# LcsNodes-Main-Controller-Board-A_02_04.net
KiCad netlist of a schematic drawn in EasyEDA
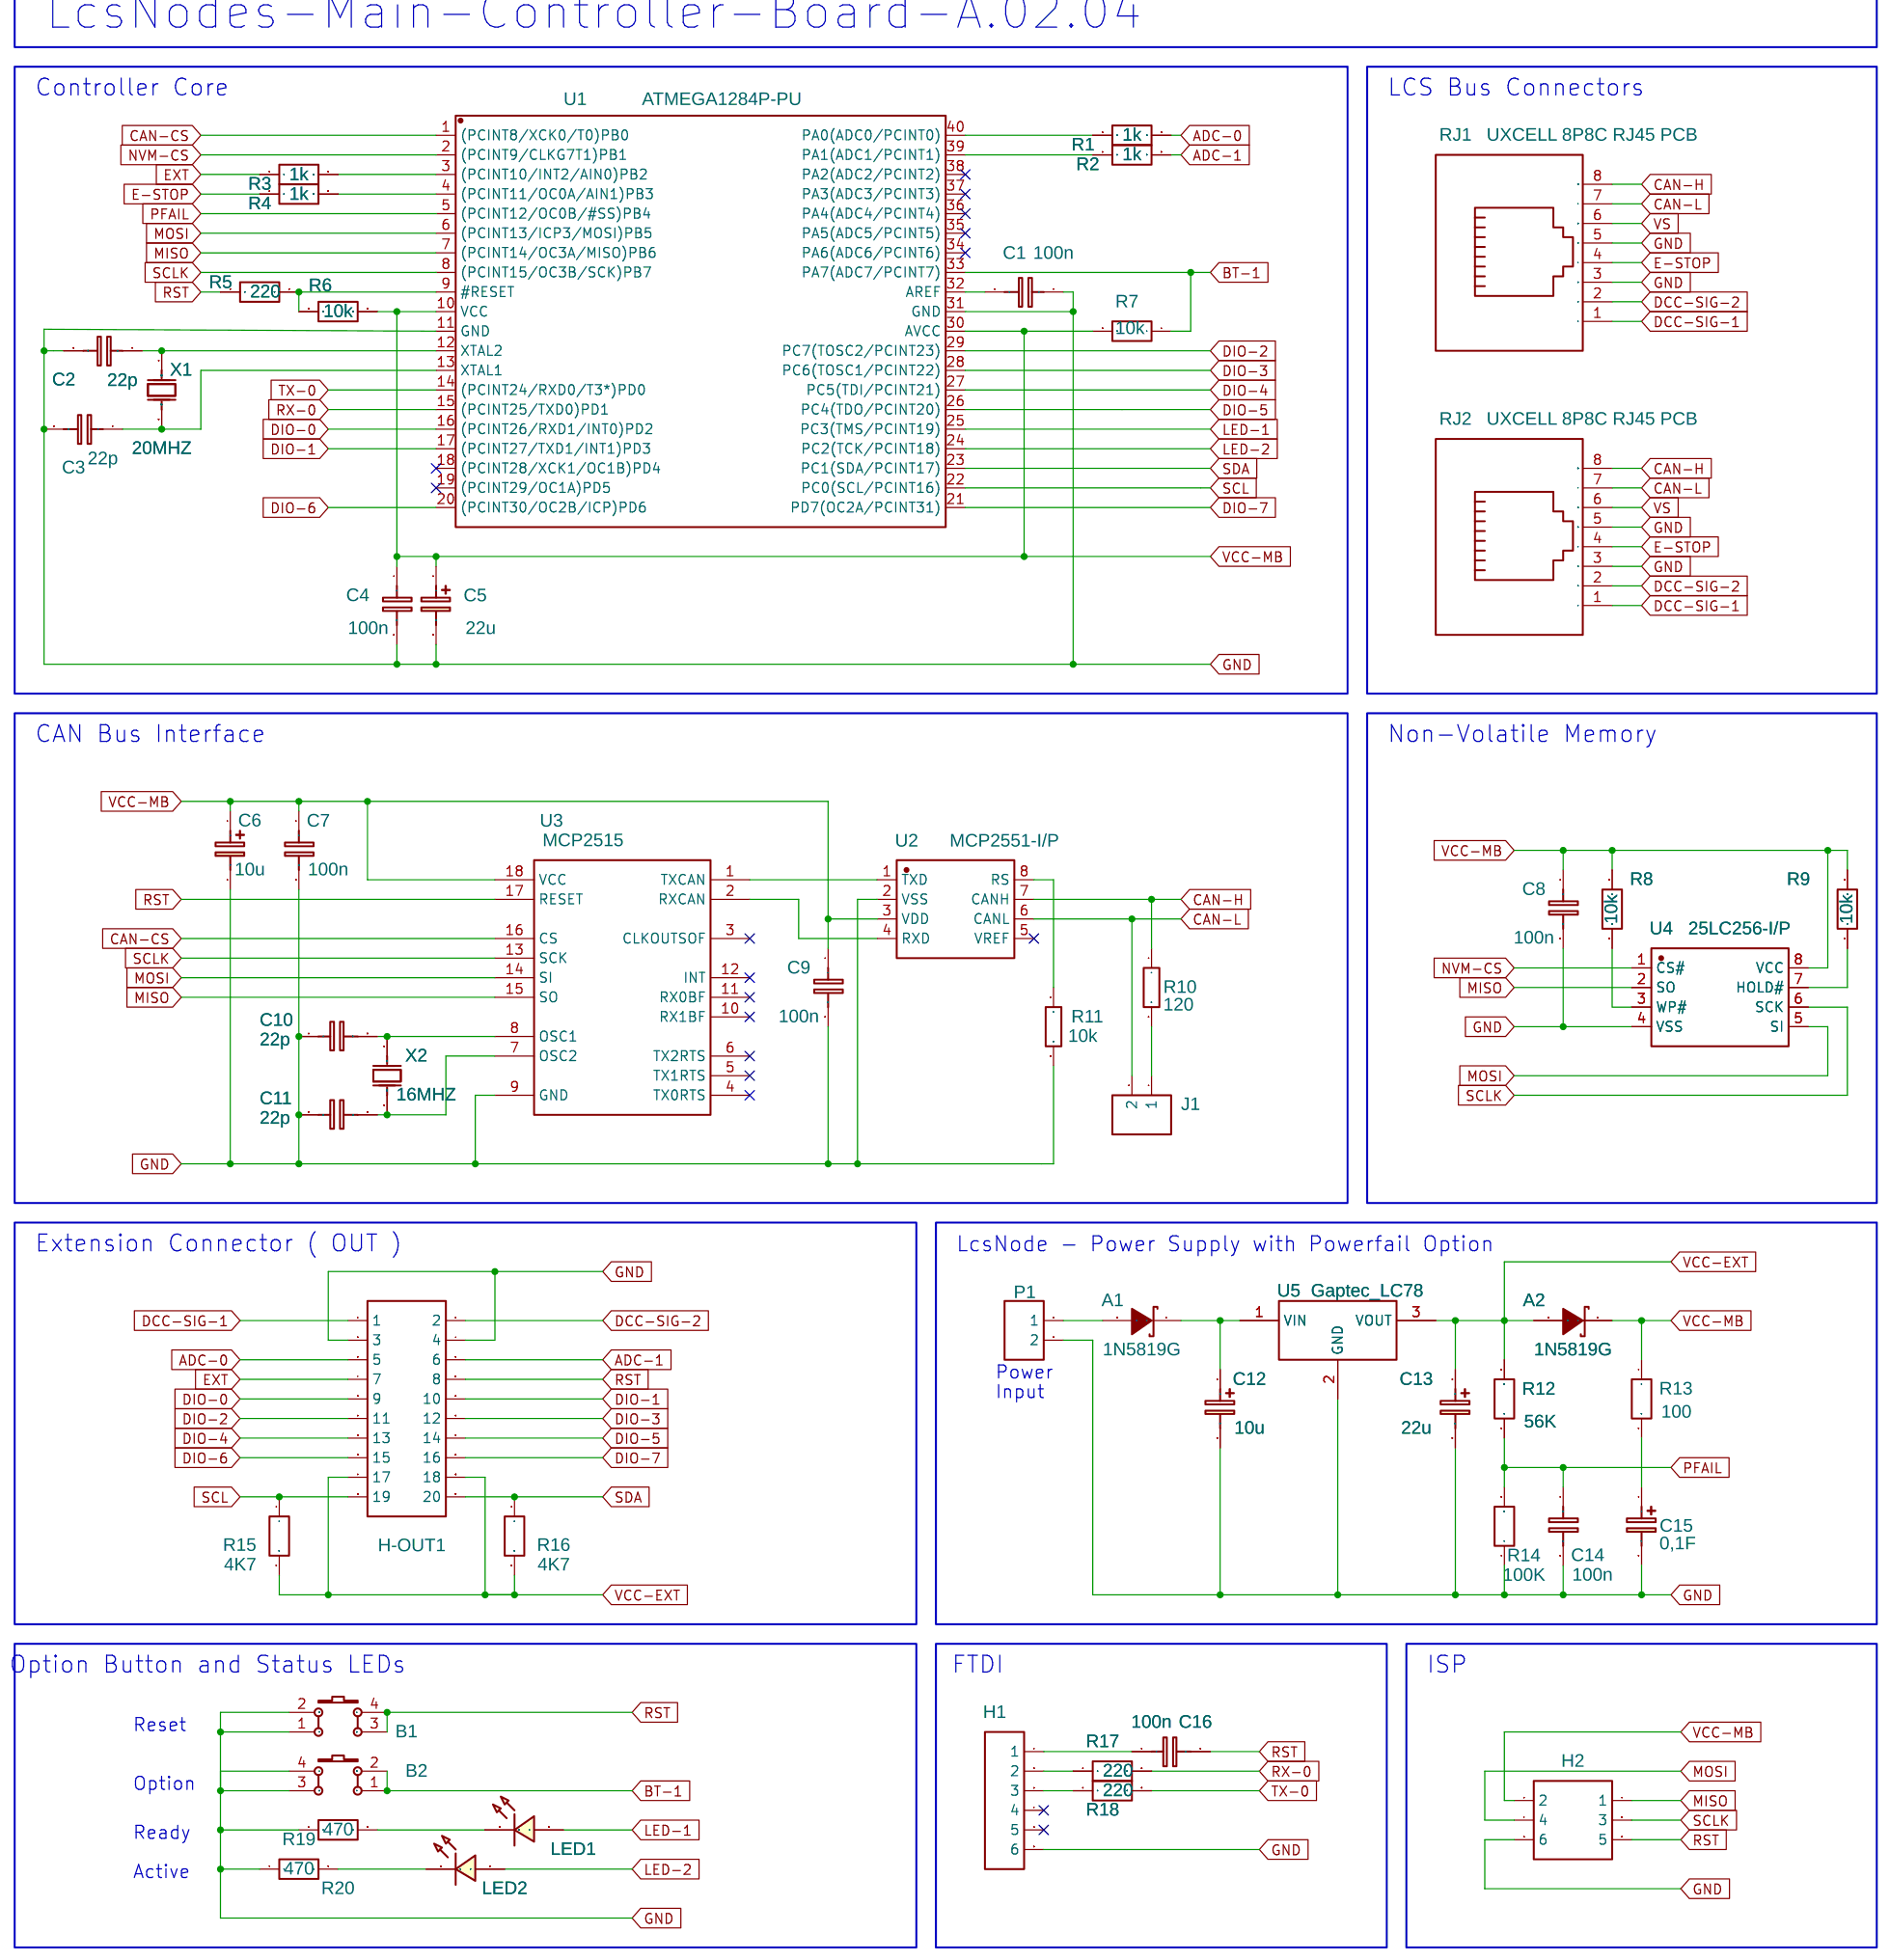
[diagram p0: schematic sheet]

(export (version "E")
  (design (tool "Eeschema 10.0.6"))
  (components
    (comp (ref "A1")
      (value "1N5819G")
      (fields (field (name "BOM_Supplier Part") "1N5819GOS-ND"))
      (libsource (lib "") (part "1N5819G"))
    )
    (comp (ref "A2")
      (value "1N5819G")
      (fields (field (name "BOM_Supplier Part") "1N5819GOS-ND"))
      (libsource (lib "") (part "1N5819G"))
    )
    (comp (ref "B1")
      (value "Reset")
      (fields
        (field (name "BOM_Manufacturer Part") "K2-1102DP-E4SW-04")
        (field (name "BOM_Supplier Part") "C136684")
      )
      (libsource (lib "") (part "K4-6×6_TH_1"))
    )
    (comp (ref "B2")
      (value "Opt")
      (fields
        (field (name "BOM_Manufacturer Part") "K2-1102DP-E4SW-04")
        (field (name "BOM_Supplier Part") "C136684")
      )
      (libsource (lib "") (part "K4-6×6_TH"))
    )
    (comp (ref "C1") (value "100n") (libsource (lib "") (part "C_RAD-0.1_EU")))
    (comp (ref "C2") (value "22p") (libsource (lib "") (part "C_0603_EU_3")))
    (comp (ref "C3") (value "22p") (libsource (lib "") (part "C_0603_EU_3")))
    (comp (ref "C4") (value "100n") (libsource (lib "") (part "C_0603_EU_4")))
    (comp (ref "C5") (value "22u") (libsource (lib "") (part "CE_TH_D4.0×F1.5_EU_2")))
    (comp (ref "C6") (value "10u") (libsource (lib "") (part "CE_TH_D4.0×F1.5_EU")))
    (comp (ref "C7") (value "100n") (libsource (lib "") (part "C_0603_EU_4")))
    (comp (ref "C8") (value "100n") (libsource (lib "") (part "C_0603_EU_2")))
    (comp (ref "C9") (value "100n") (libsource (lib "") (part "C_0603_EU_4")))
    (comp (ref "C10") (value "22p") (libsource (lib "") (part "C_0603_EU_1")))
    (comp (ref "C11") (value "22p") (libsource (lib "") (part "C_0603_EU_1")))
    (comp (ref "C12") (value "10u") (libsource (lib "") (part "CE_TH_D4.0×F1.5_EU_1")))
    (comp (ref "C13") (value "22u") (libsource (lib "") (part "CE_TH_D4.0×F1.5_EU_1")))
    (comp (ref "C14") (value "100n") (libsource (lib "") (part "C_RAD-0.2_EU")))
    (comp (ref "C15") (value "0,1F") (libsource (lib "") (part "C_Tan_SMD_A_EU")))
    (comp (ref "C16") (value "100n") (libsource (lib "") (part "C_0603_EU")))
    (comp (ref "H-OUT1")
      (value "HDR-F-2.54_2x10")
      (fields (field (name "BOM_Supplier Part") "C30867"))
      (libsource (lib "") (part "HDR-F-2.54_2x10"))
    )
    (comp (ref "H1")
      (value "HDR-F-2.54_1x6")
      (fields (field (name "BOM_Supplier Part") "C40877"))
      (libsource (lib "") (part "HDR-F-2.54_1x6"))
    )
    (comp (ref "H2")
      (value "HDR-F-2.54_2x3")
      (fields (field (name "BOM_Supplier Part") "C65114"))
      (libsource (lib "") (part "HDR-F-2.54_2x3"))
    )
    (comp (ref "J1")
      (value "HDR-M-2.54_1x2")
      (fields (field (name "BOM_Supplier Part") "C124375"))
      (libsource (lib "") (part "HDR-M-2.54_1x2"))
    )
    (comp (ref "LED1")
      (value "LED-TH-3mm_R")
      (fields
        (field (name "BOM_Manufacturer Part") "204-10SDRD/S530-A3-L")
        (field (name "BOM_Supplier Part") "C84774")
      )
      (libsource (lib "") (part "LED-TH-3mm_R"))
    )
    (comp (ref "LED2")
      (value "LED-TH-3mm_R")
      (fields
        (field (name "BOM_Manufacturer Part") "204-10SDRD/S530-A3-L")
        (field (name "BOM_Supplier Part") "C84774")
      )
      (libsource (lib "") (part "LED-TH-3mm_R"))
    )
    (comp (ref "P1") (value "CONN-TH_2P-P5.08") (libsource (lib "") (part "CONN-TH_2P-P5.08")))
    (comp (ref "R1") (value "1k") (libsource (lib "") (part "R_AXIAL-0.3_EU")))
    (comp (ref "R2") (value "1k") (libsource (lib "") (part "R_AXIAL-0.3_EU")))
    (comp (ref "R3") (value "1k") (libsource (lib "") (part "R_AXIAL-0.3_EU")))
    (comp (ref "R4") (value "1k") (libsource (lib "") (part "R_AXIAL-0.3_EU")))
    (comp (ref "R5") (value "220") (libsource (lib "") (part "R_AXIAL-0.3_EU")))
    (comp (ref "R6") (value "10k") (libsource (lib "") (part "R_AXIAL-0.3_EU")))
    (comp (ref "R7") (value "10k") (libsource (lib "") (part "R_AXIAL-0.3_EU_2")))
    (comp (ref "R8") (value "10k") (libsource (lib "") (part "R_AXIAL-0.3_EU_1")))
    (comp (ref "R9") (value "10k") (libsource (lib "") (part "R_AXIAL-0.3_EU_3")))
    (comp (ref "R10") (value "120") (libsource (lib "") (part "RESISTOR-AXIAL-0.1")))
    (comp (ref "R11") (value "10k") (libsource (lib "") (part "RESISTOR-AXIAL-0.1")))
    (comp (ref "R12") (value "56K") (libsource (lib "") (part "R_AXIAL-0.3_EU_3")))
    (comp (ref "R13") (value "100") (libsource (lib "") (part "R_AXIAL-0.3_EU_1")))
    (comp (ref "R14") (value "100K") (libsource (lib "") (part "R_AXIAL-0.3_EU_3")))
    (comp (ref "R15") (value "4K7") (libsource (lib "") (part "R_AXIAL-0.3_EU_1")))
    (comp (ref "R16") (value "4K7") (libsource (lib "") (part "R_AXIAL-0.3_EU_1")))
    (comp (ref "R17") (value "220") (libsource (lib "") (part "R_AXIAL-0.3_EU")))
    (comp (ref "R18") (value "220") (libsource (lib "") (part "R_AXIAL-0.3_EU")))
    (comp (ref "R19") (value "470") (libsource (lib "") (part "R_AXIAL-0.3_EU")))
    (comp (ref "R20") (value "470") (libsource (lib "") (part "R_AXIAL-0.3_EU")))
    (comp (ref "RJ1")
      (value "UXCELL 8P8C RJ45 PCB")
      (fields
        (field (name "BOM_Manufacturer Part") "R-RJ45R10P-B000")
        (field (name "BOM_Supplier Part") "C386758")
      )
      (libsource (lib "") (part "UXCELL 8P8C RJ45 PCB"))
    )
    (comp (ref "RJ2")
      (value "UXCELL 8P8C RJ45 PCB")
      (fields
        (field (name "BOM_Manufacturer Part") "R-RJ45R10P-B000")
        (field (name "BOM_Supplier Part") "C386758")
      )
      (libsource (lib "") (part "UXCELL 8P8C RJ45 PCB"))
    )
    (comp (ref "U1")
      (value "ATMEGA1284P-PU")
      (fields (field (name "BOM_Supplier Part") "C116839"))
      (libsource (lib "") (part "ATMEGA1284P-PU"))
    )
    (comp (ref "U2")
      (value "MCP2551-I/P")
      (fields (field (name "BOM_Supplier Part") "C411627"))
      (libsource (lib "") (part "MCP2551-I/P"))
    )
    (comp (ref "U3") (value "MCP2515") (libsource (lib "") (part "MCP2515")))
    (comp (ref "U4")
      (value "25LC256-I/P")
      (fields (field (name "BOM_Supplier Part") "C511271"))
      (libsource (lib "") (part "25LC256-I/P"))
    )
    (comp (ref "U5") (value "Gaptec_LC78") (libsource (lib "") (part "Gaptec_LC78")))
    (comp (ref "X1")
      (value "20MHZ")
      (fields
        (field (name "BOM_Manufacturer Part") "X49SD16MSD2SC")
        (field (name "BOM_Supplier Part") "C16212")
      )
      (libsource (lib "") (part "16MHZ"))
    )
    (comp (ref "X2")
      (value "16MHZ")
      (fields
        (field (name "BOM_Manufacturer Part") "X49SD16MSD2SC")
        (field (name "BOM_Supplier Part") "C16212")
      )
      (libsource (lib "") (part "16MHZ"))
    )
  )
  (nets
    (net (code "1") (name "ADC-0") (class "Default")
      (node (ref "H-OUT1") (pin "5") (pinfunction "5_5") (pintype "input"))
      (node (ref "R1") (pin "2") (pinfunction "2_2") (pintype "unspecified"))
    )
    (net (code "2") (name "ADC-1") (class "Default")
      (node (ref "H-OUT1") (pin "6") (pinfunction "6_6") (pintype "input"))
      (node (ref "R2") (pin "2") (pinfunction "2_2") (pintype "unspecified"))
    )
    (net (code "3") (name "BT-1") (class "Default")
      (node (ref "B2") (pin "1") (pinfunction "1_1") (pintype "unspecified"))
      (node (ref "B2") (pin "2") (pinfunction "2_2") (pintype "unspecified"))
      (node (ref "R7") (pin "1") (pinfunction "1_1") (pintype "unspecified"))
      (node (ref "U1") (pin "33") (pinfunction "PA7(ADC7/PCINT7)_33") (pintype "unspecified"))
    )
    (net (code "4") (name "CAN-CS") (class "Default")
      (node (ref "U1") (pin "1") (pinfunction "(PCINT8/XCK0/T0)PB0_1") (pintype "unspecified"))
      (node (ref "U3") (pin "16") (pinfunction "CS_16") (pintype "unspecified"))
    )
    (net (code "5") (name "CAN-H") (class "Default")
      (node (ref "R10") (pin "1") (pinfunction "1_1") (pintype "input"))
      (node (ref "RJ1") (pin "8") (pinfunction "8_8") (pintype "unspecified"))
      (node (ref "RJ2") (pin "8") (pinfunction "8_8") (pintype "unspecified"))
      (node (ref "U2") (pin "7") (pinfunction "CANH_7") (pintype "unspecified"))
    )
    (net (code "6") (name "CAN-L") (class "Default")
      (node (ref "J1") (pin "2") (pinfunction "2_2") (pintype "unspecified"))
      (node (ref "RJ1") (pin "7") (pinfunction "7_7") (pintype "unspecified"))
      (node (ref "RJ2") (pin "7") (pinfunction "7_7") (pintype "unspecified"))
      (node (ref "U2") (pin "6") (pinfunction "CANL_6") (pintype "unspecified"))
    )
    (net (code "7") (name "DCC-SIG-1") (class "Default")
      (node (ref "H-OUT1") (pin "1") (pinfunction "1_1") (pintype "input"))
      (node (ref "RJ1") (pin "1") (pinfunction "1_1") (pintype "unspecified"))
      (node (ref "RJ2") (pin "1") (pinfunction "1_1") (pintype "unspecified"))
    )
    (net (code "8") (name "DCC-SIG-2") (class "Default")
      (node (ref "H-OUT1") (pin "2") (pinfunction "2_2") (pintype "input"))
      (node (ref "RJ1") (pin "2") (pinfunction "2_2") (pintype "unspecified"))
      (node (ref "RJ2") (pin "2") (pinfunction "2_2") (pintype "unspecified"))
    )
    (net (code "9") (name "DIO-0") (class "Default")
      (node (ref "H-OUT1") (pin "9") (pinfunction "9_9") (pintype "input"))
      (node (ref "U1") (pin "16") (pinfunction "(PCINT26/RXD1/INT0)PD2_16") (pintype "unspecified"))
    )
    (net (code "10") (name "DIO-1") (class "Default")
      (node (ref "H-OUT1") (pin "10") (pinfunction "10_10") (pintype "input"))
      (node (ref "U1") (pin "17") (pinfunction "(PCINT27/TXD1/INT1)PD3_17") (pintype "unspecified"))
    )
    (net (code "11") (name "DIO-2") (class "Default")
      (node (ref "H-OUT1") (pin "11") (pinfunction "11_11") (pintype "input"))
      (node (ref "U1") (pin "29") (pinfunction "PC7(TOSC2/PCINT23)_29") (pintype "unspecified"))
    )
    (net (code "12") (name "DIO-3") (class "Default")
      (node (ref "H-OUT1") (pin "12") (pinfunction "12_12") (pintype "input"))
      (node (ref "U1") (pin "28") (pinfunction "PC6(TOSC1/PCINT22)_28") (pintype "unspecified"))
    )
    (net (code "13") (name "DIO-4") (class "Default")
      (node (ref "H-OUT1") (pin "13") (pinfunction "13_13") (pintype "input"))
      (node (ref "U1") (pin "27") (pinfunction "PC5(TDI/PCINT21)_27") (pintype "unspecified"))
    )
    (net (code "14") (name "DIO-5") (class "Default")
      (node (ref "H-OUT1") (pin "14") (pinfunction "14_14") (pintype "input"))
      (node (ref "U1") (pin "26") (pinfunction "PC4(TDO/PCINT20)_26") (pintype "unspecified"))
    )
    (net (code "15") (name "DIO-6") (class "Default")
      (node (ref "H-OUT1") (pin "15") (pinfunction "15_15") (pintype "input"))
      (node (ref "U1") (pin "20") (pinfunction "(PCINT30/OC2B/ICP)PD6_20") (pintype "unspecified"))
    )
    (net (code "16") (name "DIO-7") (class "Default")
      (node (ref "H-OUT1") (pin "16") (pinfunction "16_16") (pintype "input"))
      (node (ref "U1") (pin "21") (pinfunction "PD7(OC2A/PCINT31)_21") (pintype "unspecified"))
    )
    (net (code "17") (name "E-STOP") (class "Default")
      (node (ref "R4") (pin "1") (pinfunction "1_1") (pintype "unspecified"))
      (node (ref "RJ1") (pin "4") (pinfunction "4_4") (pintype "unspecified"))
      (node (ref "RJ2") (pin "4") (pinfunction "4_4") (pintype "unspecified"))
    )
    (net (code "18") (name "EXT") (class "Default")
      (node (ref "H-OUT1") (pin "7") (pinfunction "7_7") (pintype "input"))
      (node (ref "R3") (pin "1") (pinfunction "1_1") (pintype "unspecified"))
    )
    (net (code "19") (name "GND") (class "Default")
      (node (ref "B1") (pin "1") (pinfunction "1_1") (pintype "unspecified"))
      (node (ref "B1") (pin "2") (pinfunction "2_2") (pintype "unspecified"))
      (node (ref "B2") (pin "3") (pinfunction "3_3") (pintype "unspecified"))
      (node (ref "B2") (pin "4") (pinfunction "4_4") (pintype "unspecified"))
      (node (ref "C1") (pin "1") (pinfunction "1_1") (pintype "unspecified"))
      (node (ref "C10") (pin "1") (pinfunction "1_1") (pintype "unspecified"))
      (node (ref "C11") (pin "1") (pinfunction "1_1") (pintype "unspecified"))
      (node (ref "C12") (pin "2") (pinfunction "2_2") (pintype "unspecified"))
      (node (ref "C13") (pin "2") (pinfunction "2_2") (pintype "unspecified"))
      (node (ref "C14") (pin "2") (pinfunction "2_2") (pintype "unspecified"))
      (node (ref "C15") (pin "2") (pinfunction "2_2") (pintype "unspecified"))
      (node (ref "C2") (pin "2") (pinfunction "2_2") (pintype "unspecified"))
      (node (ref "C3") (pin "2") (pinfunction "2_2") (pintype "unspecified"))
      (node (ref "C4") (pin "2") (pinfunction "2_2") (pintype "unspecified"))
      (node (ref "C5") (pin "2") (pinfunction "2_2") (pintype "unspecified"))
      (node (ref "C6") (pin "2") (pinfunction "2_2") (pintype "unspecified"))
      (node (ref "C7") (pin "2") (pinfunction "2_2") (pintype "unspecified"))
      (node (ref "C8") (pin "2") (pinfunction "2_2") (pintype "unspecified"))
      (node (ref "C9") (pin "2") (pinfunction "2_2") (pintype "unspecified"))
      (node (ref "H-OUT1") (pin "3") (pinfunction "3_3") (pintype "input"))
      (node (ref "H-OUT1") (pin "4") (pinfunction "4_4") (pintype "input"))
      (node (ref "H1") (pin "6") (pinfunction "6_6") (pintype "input"))
      (node (ref "H2") (pin "6") (pinfunction "6_6") (pintype "input"))
      (node (ref "P1") (pin "2") (pinfunction "2_2") (pintype "unspecified"))
      (node (ref "R11") (pin "2") (pinfunction "2_2") (pintype "input"))
      (node (ref "R14") (pin "1") (pinfunction "1_1") (pintype "unspecified"))
      (node (ref "R19") (pin "1") (pinfunction "1_1") (pintype "unspecified"))
      (node (ref "R20") (pin "1") (pinfunction "1_1") (pintype "unspecified"))
      (node (ref "RJ1") (pin "3") (pinfunction "3_3") (pintype "unspecified"))
      (node (ref "RJ1") (pin "5") (pinfunction "5_5") (pintype "unspecified"))
      (node (ref "RJ2") (pin "3") (pinfunction "3_3") (pintype "unspecified"))
      (node (ref "RJ2") (pin "5") (pinfunction "5_5") (pintype "unspecified"))
      (node (ref "U1") (pin "11") (pinfunction "GND_11") (pintype "unspecified"))
      (node (ref "U1") (pin "31") (pinfunction "GND_31") (pintype "unspecified"))
      (node (ref "U2") (pin "2") (pinfunction "VSS_2") (pintype "unspecified"))
      (node (ref "U3") (pin "9") (pinfunction "GND_9") (pintype "passive"))
      (node (ref "U4") (pin "4") (pinfunction "VSS_4") (pintype "unspecified"))
      (node (ref "U5") (pin "2") (pinfunction "GND_2") (pintype "unspecified"))
    )
    (net (code "20") (name "LED-1") (class "Default")
      (node (ref "LED1") (pin "1") (pinfunction "1_1") (pintype "unspecified"))
      (node (ref "U1") (pin "25") (pinfunction "PC3(TMS/PCINT19)_25") (pintype "unspecified"))
    )
    (net (code "21") (name "LED-2") (class "Default")
      (node (ref "LED2") (pin "1") (pinfunction "1_1") (pintype "unspecified"))
      (node (ref "U1") (pin "24") (pinfunction "PC2(TCK/PCINT18)_24") (pintype "unspecified"))
    )
    (net (code "22") (name "MISO") (class "Default")
      (node (ref "H2") (pin "1") (pinfunction "1_1") (pintype "input"))
      (node (ref "U1") (pin "7") (pinfunction "(PCINT14/OC3A/MISO)PB6_7") (pintype "unspecified"))
      (node (ref "U3") (pin "15") (pinfunction "SO_15") (pintype "output"))
      (node (ref "U4") (pin "2") (pinfunction "SO_2") (pintype "unspecified"))
    )
    (net (code "23") (name "MOSI") (class "Default")
      (node (ref "H2") (pin "4") (pinfunction "4_4") (pintype "input"))
      (node (ref "U1") (pin "6") (pinfunction "(PCINT13/ICP3/MOSI)PB5_6") (pintype "unspecified"))
      (node (ref "U3") (pin "14") (pinfunction "SI_14") (pintype "unspecified"))
      (node (ref "U4") (pin "5") (pinfunction "SI_5") (pintype "unspecified"))
    )
    (net (code "24") (name "NVM-CS") (class "Default")
      (node (ref "U1") (pin "2") (pinfunction "(PCINT9/CLKG7T1)PB1_2") (pintype "unspecified"))
      (node (ref "U4") (pin "1") (pinfunction "CS#_1") (pintype "unspecified"))
    )
    (net (code "25") (name "Net-(A1-A)") (class "Default")
      (node (ref "A1") (pin "2") (pinfunction "A_2") (pintype "unspecified"))
      (node (ref "P1") (pin "1") (pinfunction "1_1") (pintype "unspecified"))
    )
    (net (code "26") (name "Net-(A1-K)") (class "Default")
      (node (ref "A1") (pin "1") (pinfunction "K_1") (pintype "unspecified"))
      (node (ref "C12") (pin "1") (pinfunction "1_1") (pintype "unspecified"))
      (node (ref "U5") (pin "1") (pinfunction "VIN_1") (pintype "unspecified"))
    )
    (net (code "27") (name "Net-(C15-Pad1)") (class "Default")
      (node (ref "C15") (pin "1") (pinfunction "1_1") (pintype "unspecified"))
      (node (ref "R13") (pin "2") (pinfunction "2_2") (pintype "unspecified"))
    )
    (net (code "28") (name "Net-(C16-Pad1)") (class "Default")
      (node (ref "C16") (pin "1") (pinfunction "1_1") (pintype "unspecified"))
      (node (ref "H1") (pin "1") (pinfunction "1_1") (pintype "input"))
    )
    (net (code "29") (name "Net-(H1-Pad2)") (class "Default")
      (node (ref "H1") (pin "2") (pinfunction "2_2") (pintype "input"))
      (node (ref "R17") (pin "1") (pinfunction "1_1") (pintype "unspecified"))
    )
    (net (code "30") (name "Net-(H1-Pad3)") (class "Default")
      (node (ref "H1") (pin "3") (pinfunction "3_3") (pintype "input"))
      (node (ref "R18") (pin "1") (pinfunction "1_1") (pintype "unspecified"))
    )
    (net (code "31") (name "Net-(J1-Pad1)") (class "Default")
      (node (ref "J1") (pin "1") (pinfunction "1_1") (pintype "unspecified"))
      (node (ref "R10") (pin "2") (pinfunction "2_2") (pintype "input"))
    )
    (net (code "32") (name "Net-(LED1-Pad2)") (class "Default")
      (node (ref "LED1") (pin "2") (pinfunction "2_2") (pintype "unspecified"))
      (node (ref "R19") (pin "2") (pinfunction "2_2") (pintype "unspecified"))
    )
    (net (code "33") (name "Net-(LED2-Pad2)") (class "Default")
      (node (ref "LED2") (pin "2") (pinfunction "2_2") (pintype "unspecified"))
      (node (ref "R20") (pin "2") (pinfunction "2_2") (pintype "unspecified"))
    )
    (net (code "34") (name "Net-(U1-#RESET)") (class "Default")
      (node (ref "R5") (pin "2") (pinfunction "2_2") (pintype "unspecified"))
      (node (ref "R6") (pin "1") (pinfunction "1_1") (pintype "unspecified"))
      (node (ref "U1") (pin "9") (pinfunction "#RESET_9") (pintype "unspecified"))
    )
    (net (code "35") (name "Net-(U1-(PCINT10{slash}INT2{slash}AIN0)PB2)") (class "Default")
      (node (ref "R3") (pin "2") (pinfunction "2_2") (pintype "unspecified"))
      (node (ref "U1") (pin "3") (pinfunction "(PCINT10/INT2/AIN0)PB2_3") (pintype "unspecified"))
    )
    (net (code "36") (name "Net-(U1-(PCINT11{slash}OC0A{slash}AIN1)PB3)") (class "Default")
      (node (ref "R4") (pin "2") (pinfunction "2_2") (pintype "unspecified"))
      (node (ref "U1") (pin "4") (pinfunction "(PCINT11/OC0A/AIN1)PB3_4") (pintype "unspecified"))
    )
    (net (code "37") (name "Net-(U1-AREF)") (class "Default")
      (node (ref "C1") (pin "2") (pinfunction "2_2") (pintype "unspecified"))
      (node (ref "U1") (pin "32") (pinfunction "AREF_32") (pintype "unspecified"))
    )
    (net (code "38") (name "Net-(U1-PA0(ADC0{slash}PCINT0))") (class "Default")
      (node (ref "R1") (pin "1") (pinfunction "1_1") (pintype "unspecified"))
      (node (ref "U1") (pin "40") (pinfunction "PA0(ADC0/PCINT0)_40") (pintype "unspecified"))
    )
    (net (code "39") (name "Net-(U1-PA1(ADC1{slash}PCINT1))") (class "Default")
      (node (ref "R2") (pin "1") (pinfunction "1_1") (pintype "unspecified"))
      (node (ref "U1") (pin "39") (pinfunction "PA1(ADC1/PCINT1)_39") (pintype "unspecified"))
    )
    (net (code "40") (name "Net-(U1-XTAL1)") (class "Default")
      (node (ref "C3") (pin "1") (pinfunction "1_1") (pintype "unspecified"))
      (node (ref "U1") (pin "13") (pinfunction "XTAL1_13") (pintype "unspecified"))
      (node (ref "X1") (pin "2") (pinfunction "OSC2_2") (pintype "input"))
    )
    (net (code "41") (name "Net-(U1-XTAL2)") (class "Default")
      (node (ref "C2") (pin "1") (pinfunction "1_1") (pintype "unspecified"))
      (node (ref "U1") (pin "12") (pinfunction "XTAL2_12") (pintype "unspecified"))
      (node (ref "X1") (pin "1") (pinfunction "OSC1_1") (pintype "input"))
    )
    (net (code "42") (name "Net-(U2-RS)") (class "Default")
      (node (ref "R11") (pin "1") (pinfunction "1_1") (pintype "input"))
      (node (ref "U2") (pin "8") (pinfunction "RS_8") (pintype "unspecified"))
    )
    (net (code "43") (name "Net-(U2-RXD)") (class "Default")
      (node (ref "U2") (pin "4") (pinfunction "RXD_4") (pintype "unspecified"))
      (node (ref "U3") (pin "2") (pinfunction "RXCAN_2") (pintype "unspecified"))
    )
    (net (code "44") (name "Net-(U2-TXD)") (class "Default")
      (node (ref "U2") (pin "1") (pinfunction "TXD_1") (pintype "unspecified"))
      (node (ref "U3") (pin "1") (pinfunction "TXCAN_1") (pintype "output"))
    )
    (net (code "45") (name "Net-(U3-OSC1)") (class "Default")
      (node (ref "C10") (pin "2") (pinfunction "2_2") (pintype "unspecified"))
      (node (ref "U3") (pin "8") (pinfunction "OSC1_8") (pintype "unspecified"))
      (node (ref "X2") (pin "1") (pinfunction "OSC1_1") (pintype "input"))
    )
    (net (code "46") (name "Net-(U3-OSC2)") (class "Default")
      (node (ref "C11") (pin "2") (pinfunction "2_2") (pintype "unspecified"))
      (node (ref "U3") (pin "7") (pinfunction "OSC2_7") (pintype "output"))
      (node (ref "X2") (pin "2") (pinfunction "OSC2_2") (pintype "input"))
    )
    (net (code "47") (name "Net-(U4-HOLD#)") (class "Default")
      (node (ref "R9") (pin "1") (pinfunction "1_1") (pintype "unspecified"))
      (node (ref "U4") (pin "7") (pinfunction "HOLD#_7") (pintype "unspecified"))
    )
    (net (code "48") (name "Net-(U4-WP#)") (class "Default")
      (node (ref "R8") (pin "2") (pinfunction "2_2") (pintype "unspecified"))
      (node (ref "U4") (pin "3") (pinfunction "WP#_3") (pintype "unspecified"))
    )
    (net (code "49") (name "PFAIL") (class "Default")
      (node (ref "C14") (pin "1") (pinfunction "1_1") (pintype "unspecified"))
      (node (ref "R12") (pin "1") (pinfunction "1_1") (pintype "unspecified"))
      (node (ref "R14") (pin "2") (pinfunction "2_2") (pintype "unspecified"))
      (node (ref "U1") (pin "5") (pinfunction "(PCINT12/OC0B/#SS)PB4_5") (pintype "unspecified"))
    )
    (net (code "50") (name "RST") (class "Default")
      (node (ref "B1") (pin "3") (pinfunction "3_3") (pintype "unspecified"))
      (node (ref "B1") (pin "4") (pinfunction "4_4") (pintype "unspecified"))
      (node (ref "C16") (pin "2") (pinfunction "2_2") (pintype "unspecified"))
      (node (ref "H-OUT1") (pin "8") (pinfunction "8_8") (pintype "input"))
      (node (ref "H2") (pin "5") (pinfunction "5_5") (pintype "input"))
      (node (ref "R5") (pin "1") (pinfunction "1_1") (pintype "unspecified"))
      (node (ref "U3") (pin "17") (pinfunction "RESET_17") (pintype "unspecified"))
    )
    (net (code "51") (name "RX-0") (class "Default")
      (node (ref "R17") (pin "2") (pinfunction "2_2") (pintype "unspecified"))
      (node (ref "U1") (pin "15") (pinfunction "(PCINT25/TXD0)PD1_15") (pintype "unspecified"))
    )
    (net (code "52") (name "SCL") (class "Default")
      (node (ref "H-OUT1") (pin "19") (pinfunction "19_19") (pintype "input"))
      (node (ref "R15") (pin "1") (pinfunction "1_1") (pintype "unspecified"))
      (node (ref "U1") (pin "22") (pinfunction "PC0(SCL/PCINT16)_22") (pintype "unspecified"))
    )
    (net (code "53") (name "SCLK") (class "Default")
      (node (ref "H2") (pin "3") (pinfunction "3_3") (pintype "input"))
      (node (ref "U1") (pin "8") (pinfunction "(PCINT15/OC3B/SCK)PB7_8") (pintype "unspecified"))
      (node (ref "U3") (pin "13") (pinfunction "SCK_13") (pintype "unspecified"))
      (node (ref "U4") (pin "6") (pinfunction "SCK_6") (pintype "unspecified"))
    )
    (net (code "54") (name "SDA") (class "Default")
      (node (ref "H-OUT1") (pin "20") (pinfunction "20_20") (pintype "input"))
      (node (ref "R16") (pin "1") (pinfunction "1_1") (pintype "unspecified"))
      (node (ref "U1") (pin "23") (pinfunction "PC1(SDA/PCINT17)_23") (pintype "unspecified"))
    )
    (net (code "55") (name "TX-0") (class "Default")
      (node (ref "R18") (pin "2") (pinfunction "2_2") (pintype "unspecified"))
      (node (ref "U1") (pin "14") (pinfunction "(PCINT24/RXD0/T3*)PD0_14") (pintype "unspecified"))
    )
    (net (code "56") (name "VCC-EXT") (class "Default")
      (node (ref "A2") (pin "2") (pinfunction "A_2") (pintype "unspecified"))
      (node (ref "C13") (pin "1") (pinfunction "1_1") (pintype "unspecified"))
      (node (ref "H-OUT1") (pin "17") (pinfunction "17_17") (pintype "input"))
      (node (ref "H-OUT1") (pin "18") (pinfunction "18_18") (pintype "input"))
      (node (ref "R12") (pin "2") (pinfunction "2_2") (pintype "unspecified"))
      (node (ref "R15") (pin "2") (pinfunction "2_2") (pintype "unspecified"))
      (node (ref "R16") (pin "2") (pinfunction "2_2") (pintype "unspecified"))
      (node (ref "U5") (pin "3") (pinfunction "VOUT_3") (pintype "unspecified"))
    )
    (net (code "57") (name "VCC-MB") (class "Default")
      (node (ref "A2") (pin "1") (pinfunction "K_1") (pintype "unspecified"))
      (node (ref "C4") (pin "1") (pinfunction "1_1") (pintype "unspecified"))
      (node (ref "C5") (pin "1") (pinfunction "1_1") (pintype "unspecified"))
      (node (ref "C6") (pin "1") (pinfunction "1_1") (pintype "unspecified"))
      (node (ref "C7") (pin "1") (pinfunction "1_1") (pintype "unspecified"))
      (node (ref "C8") (pin "1") (pinfunction "1_1") (pintype "unspecified"))
      (node (ref "C9") (pin "1") (pinfunction "1_1") (pintype "unspecified"))
      (node (ref "H2") (pin "2") (pinfunction "2_2") (pintype "input"))
      (node (ref "R13") (pin "1") (pinfunction "1_1") (pintype "unspecified"))
      (node (ref "R6") (pin "2") (pinfunction "2_2") (pintype "unspecified"))
      (node (ref "R7") (pin "2") (pinfunction "2_2") (pintype "unspecified"))
      (node (ref "R8") (pin "1") (pinfunction "1_1") (pintype "unspecified"))
      (node (ref "R9") (pin "2") (pinfunction "2_2") (pintype "unspecified"))
      (node (ref "U1") (pin "10") (pinfunction "VCC_10") (pintype "unspecified"))
      (node (ref "U1") (pin "30") (pinfunction "AVCC_30") (pintype "unspecified"))
      (node (ref "U2") (pin "3") (pinfunction "VDD_3") (pintype "unspecified"))
      (node (ref "U3") (pin "18") (pinfunction "VCC_18") (pintype "passive"))
      (node (ref "U4") (pin "8") (pinfunction "VCC_8") (pintype "unspecified"))
    )
    (net (code "58") (name "VS") (class "Default")
      (node (ref "RJ1") (pin "6") (pinfunction "6_6") (pintype "unspecified"))
      (node (ref "RJ2") (pin "6") (pinfunction "6_6") (pintype "unspecified"))
    )
    (net (code "59") (name "unconnected-(H1-Pad4)") (class "Default")
      (node (ref "H1") (pin "4") (pinfunction "4_4") (pintype "input+no_connect"))
    )
    (net (code "60") (name "unconnected-(H1-Pad5)") (class "Default")
      (node (ref "H1") (pin "5") (pinfunction "5_5") (pintype "input+no_connect"))
    )
    (net (code "61") (name "unconnected-(U1-(PCINT28{slash}XCK1{slash}OC1B)PD4-Pad18)") (class "Default")
      (node (ref "U1") (pin "18") (pinfunction "(PCINT28/XCK1/OC1B)PD4_18") (pintype "unspecified+no_connect"))
    )
    (net (code "62") (name "unconnected-(U1-(PCINT29{slash}OC1A)PD5-Pad19)") (class "Default")
      (node (ref "U1") (pin "19") (pinfunction "(PCINT29/OC1A)PD5_19") (pintype "unspecified+no_connect"))
    )
    (net (code "63") (name "unconnected-(U1-PA2(ADC2{slash}PCINT2)-Pad38)") (class "Default")
      (node (ref "U1") (pin "38") (pinfunction "PA2(ADC2/PCINT2)_38") (pintype "unspecified+no_connect"))
    )
    (net (code "64") (name "unconnected-(U1-PA3(ADC3{slash}PCINT3)-Pad37)") (class "Default")
      (node (ref "U1") (pin "37") (pinfunction "PA3(ADC3/PCINT3)_37") (pintype "unspecified+no_connect"))
    )
    (net (code "65") (name "unconnected-(U1-PA4(ADC4{slash}PCINT4)-Pad36)") (class "Default")
      (node (ref "U1") (pin "36") (pinfunction "PA4(ADC4/PCINT4)_36") (pintype "unspecified+no_connect"))
    )
    (net (code "66") (name "unconnected-(U1-PA5(ADC5{slash}PCINT5)-Pad35)") (class "Default")
      (node (ref "U1") (pin "35") (pinfunction "PA5(ADC5/PCINT5)_35") (pintype "unspecified+no_connect"))
    )
    (net (code "67") (name "unconnected-(U1-PA6(ADC6{slash}PCINT6)-Pad34)") (class "Default")
      (node (ref "U1") (pin "34") (pinfunction "PA6(ADC6/PCINT6)_34") (pintype "unspecified+no_connect"))
    )
    (net (code "68") (name "unconnected-(U2-VREF-Pad5)") (class "Default")
      (node (ref "U2") (pin "5") (pinfunction "VREF_5") (pintype "unspecified+no_connect"))
    )
    (net (code "69") (name "unconnected-(U3-CLKOUTSOF-Pad3)") (class "Default")
      (node (ref "U3") (pin "3") (pinfunction "CLKOUTSOF_3") (pintype "output+no_connect"))
    )
    (net (code "70") (name "unconnected-(U3-INT-Pad12)") (class "Default")
      (node (ref "U3") (pin "12") (pinfunction "INT_12") (pintype "output+no_connect"))
    )
    (net (code "71") (name "unconnected-(U3-RX0BF-Pad11)") (class "Default")
      (node (ref "U3") (pin "11") (pinfunction "RX0BF_11") (pintype "output+no_connect"))
    )
    (net (code "72") (name "unconnected-(U3-RX1BF-Pad10)") (class "Default")
      (node (ref "U3") (pin "10") (pinfunction "RX1BF_10") (pintype "output+no_connect"))
    )
    (net (code "73") (name "unconnected-(U3-TX0RTS-Pad4)") (class "Default")
      (node (ref "U3") (pin "4") (pinfunction "TX0RTS_4") (pintype "unspecified+no_connect"))
    )
    (net (code "74") (name "unconnected-(U3-TX1RTS-Pad5)") (class "Default")
      (node (ref "U3") (pin "5") (pinfunction "TX1RTS_5") (pintype "unspecified+no_connect"))
    )
    (net (code "75") (name "unconnected-(U3-TX2RTS-Pad6)") (class "Default")
      (node (ref "U3") (pin "6") (pinfunction "TX2RTS_6") (pintype "unspecified+no_connect"))
    )
  )
)
